# CurrentMonitorOnAStick.net
KiCad netlist of a schematic drawn in EAGLE
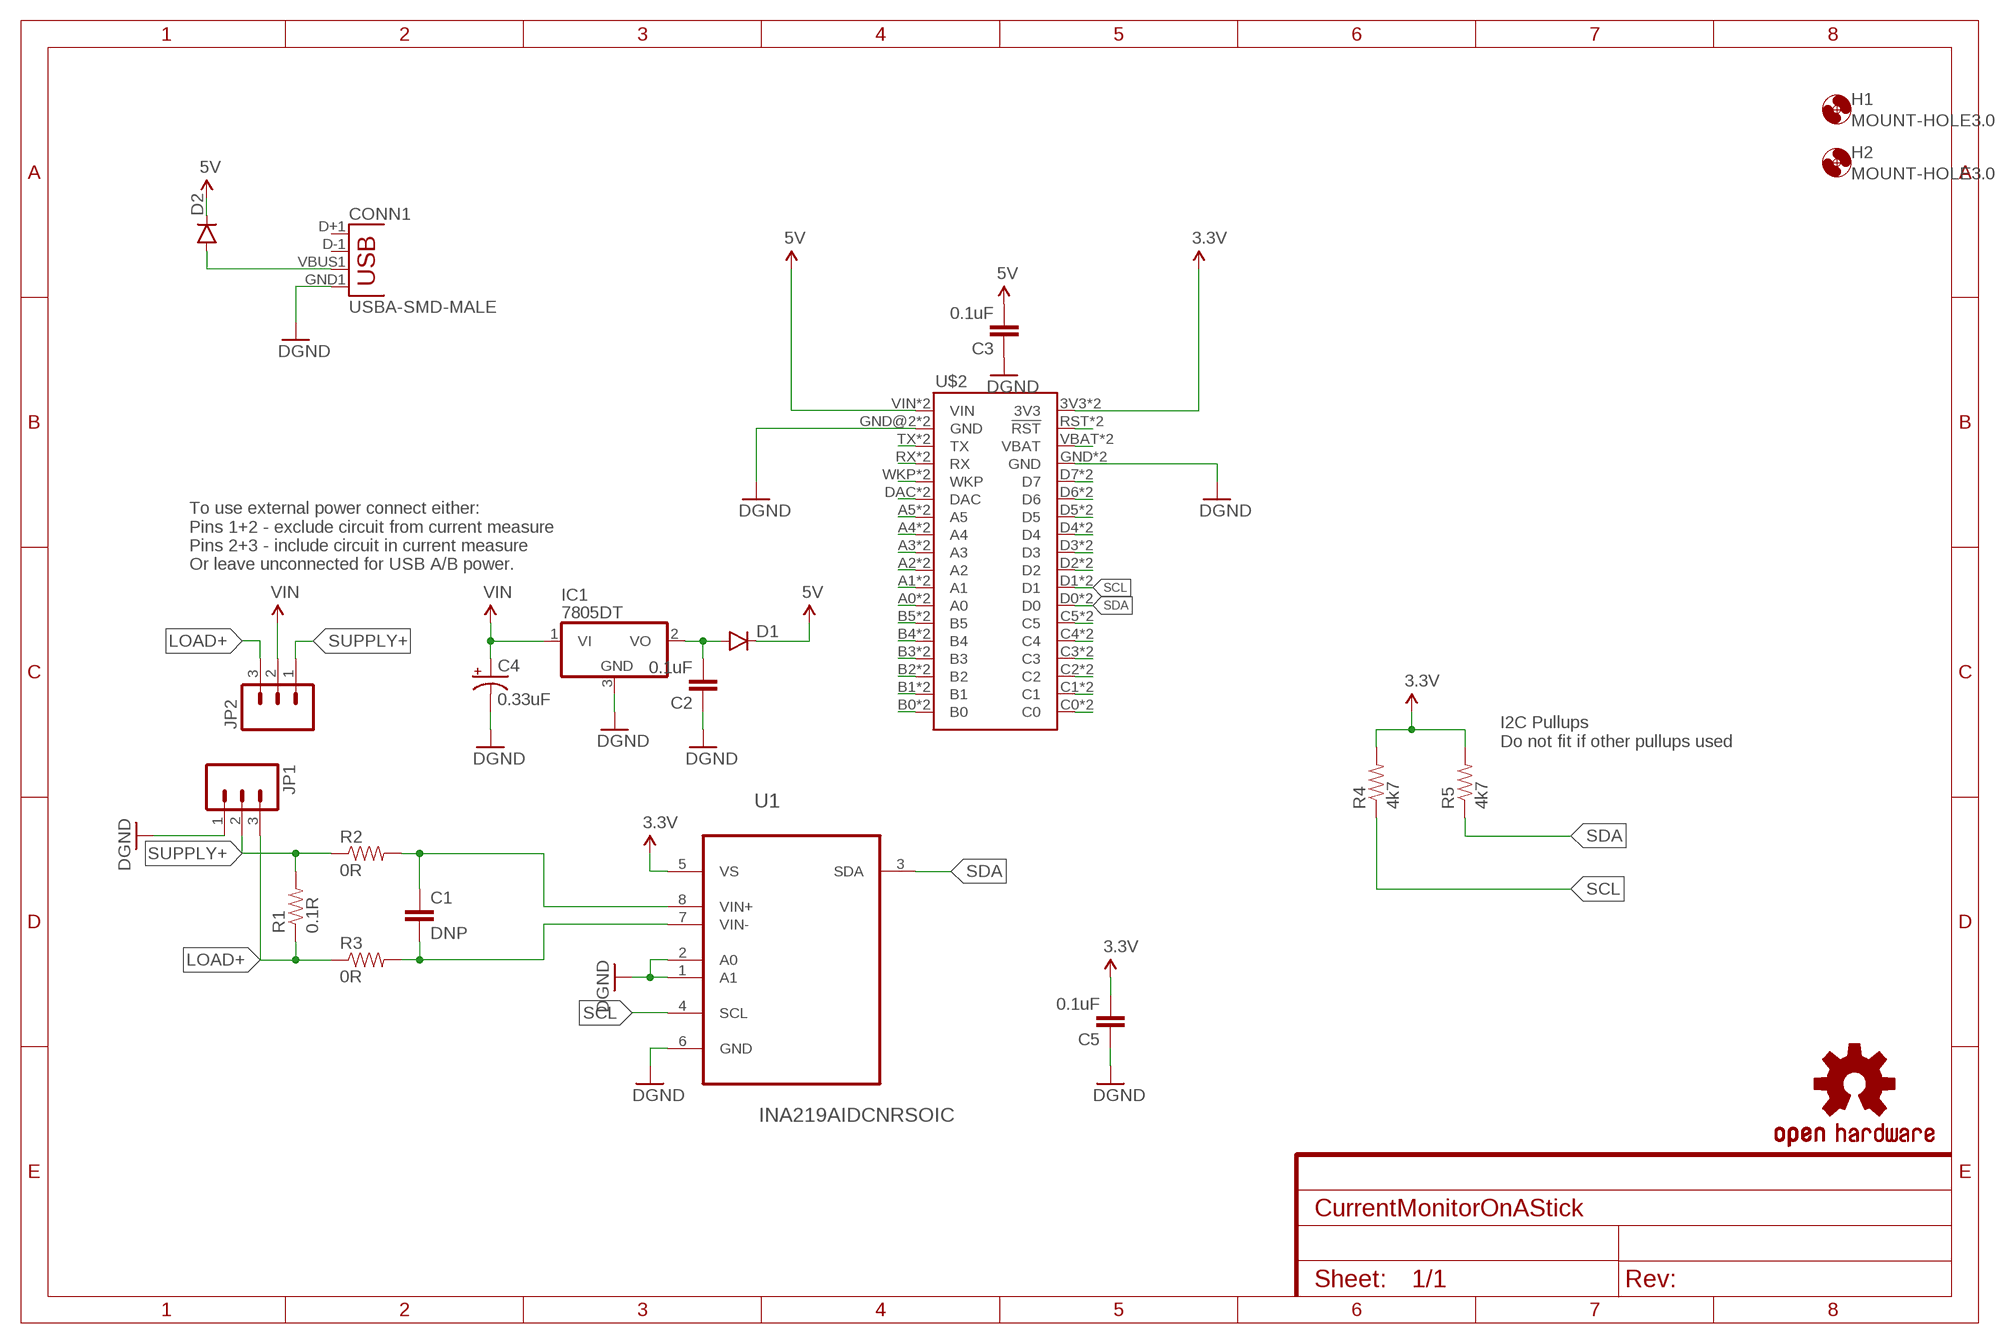
[diagram p0: schematic, sheet 1]

(export (version "E")
  (design (tool "Eeschema 10.0.6"))
  (components
    (comp (ref "C1")
      (value "DNP")
      (footprint "eagle-import:0805")
      (libsource (lib "eagle-import") (part "CAP0805"))
    )
    (comp (ref "C2")
      (value "0.1uF")
      (footprint "eagle-import:0805")
      (libsource (lib "eagle-import") (part "SparkFun-Passives_CAP0805"))
    )
    (comp (ref "C3")
      (value "0.1uF")
      (footprint "eagle-import:0805")
      (libsource (lib "eagle-import") (part "SparkFun-Passives_CAP0805"))
    )
    (comp (ref "C4")
      (value "0.33uF")
      (footprint "eagle-import:EIA3216")
      (libsource (lib "eagle-import") (part "10UF-16V-10%(TANT)"))
    )
    (comp (ref "C5")
      (value "0.1uF")
      (footprint "eagle-import:0805")
      (libsource (lib "eagle-import") (part "SparkFun-Passives_CAP0805"))
    )
    (comp (ref "CONN1")
      (value "USBA-SMD-MALE")
      (footprint "eagle-import:USB-A-SMT-MALE")
      (libsource (lib "eagle-import") (part "USBA-SMD-MALE"))
    )
    (comp (ref "D1")
      (value "DIODESMA")
      (footprint "eagle-import:SMA-DIODE")
      (libsource (lib "eagle-import") (part "DIODESMA"))
    )
    (comp (ref "D2")
      (value "DIODESMA")
      (footprint "eagle-import:SMA-DIODE")
      (libsource (lib "eagle-import") (part "DIODESMA"))
    )
    (comp (ref "H1")
      (value "MOUNT-HOLE3.0")
      (footprint "eagle-import:3,0")
      (libsource (lib "eagle-import") (part "MOUNT-HOLE3.0"))
    )
    (comp (ref "H2")
      (value "MOUNT-HOLE3.0")
      (footprint "eagle-import:3,0")
      (libsource (lib "eagle-import") (part "MOUNT-HOLE3.0"))
    )
    (comp (ref "IC1")
      (value "7805DT")
      (footprint "eagle-import:TO252")
      (libsource (lib "eagle-import") (part "78DT05"))
    )
    (comp (ref "JP1")
      (value "M03-SCREW-5MM")
      (footprint "eagle-import:SCREWTERMINAL-5MM-3")
      (libsource (lib "eagle-import") (part "M03-SCREW-5MM"))
    )
    (comp (ref "JP2")
      (value "M03PTH")
      (footprint "eagle-import:1X03")
      (libsource (lib "eagle-import") (part "M03PTH"))
    )
    (comp (ref "LOGO2")
      (value "OSHW-LOGOS")
      (footprint "eagle-import:OSHW-LOGO-S")
      (libsource (lib "eagle-import") (part "OSHW-LOGOS"))
    )
    (comp (ref "R1")
      (value "0.1R")
      (footprint "eagle-import:2512")
      (libsource (lib "eagle-import") (part "0.001OHM-3W-1%(2512)3W/1%"))
    )
    (comp (ref "R2")
      (value "0R")
      (footprint "eagle-import:0805")
      (libsource (lib "eagle-import") (part "RESISTOR0805-RES"))
    )
    (comp (ref "R3")
      (value "0R")
      (footprint "eagle-import:0805")
      (libsource (lib "eagle-import") (part "RESISTOR0805-RES"))
    )
    (comp (ref "R4")
      (value "4k7")
      (footprint "eagle-import:0805")
      (libsource (lib "eagle-import") (part "RESISTOR0805-RES"))
    )
    (comp (ref "R5")
      (value "4k7")
      (footprint "eagle-import:0805")
      (libsource (lib "eagle-import") (part "RESISTOR0805-RES"))
    )
    (comp (ref "U$2")
      (value "ELECTRONDUALNAMED")
      (footprint "eagle-import:ELECTRON_SIMPLE_SILK_NAMES_DUAL")
      (libsource (lib "eagle-import") (part "ELECTRONDUALNAMED"))
    )
    (comp (ref "U1")
      (value "INA219AIDCNRSOIC")
      (footprint "eagle-import:SO08")
      (libsource (lib "eagle-import") (part "INA219AIDCNRSOIC"))
    )
  )
  (nets
    (net (code "1") (name "3.3V") (class "Default")
      (node (ref "C5") (pin "2") (pinfunction "2_2") (pintype "passive"))
      (node (ref "R4") (pin "2") (pinfunction "2_2") (pintype "passive"))
      (node (ref "R5") (pin "2") (pinfunction "2_2") (pintype "passive"))
      (node (ref "U$2") (pin "3V3") (pinfunction "3V3_3V3") (pintype "power_in"))
      (node (ref "U$2") (pin "3V3_1") (pinfunction "3V3_3V3_1") (pintype "power_in"))
      (node (ref "U1") (pin "5") (pinfunction "VS_5") (pintype "power_in"))
    )
    (net (code "2") (name "5V") (class "Default")
      (node (ref "C3") (pin "2") (pinfunction "2_2") (pintype "passive"))
      (node (ref "D1") (pin "C") (pinfunction "C_C") (pintype "passive"))
      (node (ref "D2") (pin "C") (pinfunction "C_C") (pintype "passive"))
      (node (ref "U$2") (pin "VIN") (pinfunction "VIN_VIN") (pintype "power_in"))
      (node (ref "U$2") (pin "VIN_1B") (pinfunction "VIN_VIN_1B") (pintype "power_in"))
    )
    (net (code "3") (name "DGND") (class "Default")
      (node (ref "C2") (pin "1") (pinfunction "1_1") (pintype "passive"))
      (node (ref "C3") (pin "1") (pinfunction "1_1") (pintype "passive"))
      (node (ref "C4") (pin "C") (pinfunction "-_C") (pintype "passive"))
      (node (ref "C5") (pin "1") (pinfunction "1_1") (pintype "passive"))
      (node (ref "CONN1") (pin "GND1") (pinfunction "GND_GND1") (pintype "bidirectional"))
      (node (ref "IC1") (pin "3") (pinfunction "GND_3") (pintype "passive"))
      (node (ref "JP1") (pin "1") (pinfunction "1_1") (pintype "passive"))
      (node (ref "U$2") (pin "GND") (pinfunction "GND_GND") (pintype "power_in"))
      (node (ref "U$2") (pin "GND@2") (pinfunction "GND_GND@2") (pintype "power_in"))
      (node (ref "U$2") (pin "GND_1") (pinfunction "GND_GND_1") (pintype "power_in"))
      (node (ref "U$2") (pin "GND_1B") (pinfunction "GND_GND_1B") (pintype "power_in"))
      (node (ref "U1") (pin "1") (pinfunction "A1_1") (pintype "input"))
      (node (ref "U1") (pin "2") (pinfunction "A0_2") (pintype "input"))
      (node (ref "U1") (pin "6") (pinfunction "GND_6") (pintype "passive"))
    )
    (net (code "4") (name "LOAD+") (class "Default")
      (node (ref "JP1") (pin "3") (pinfunction "3_3") (pintype "passive"))
      (node (ref "JP2") (pin "3") (pinfunction "3_3") (pintype "passive"))
      (node (ref "R1") (pin "1") (pinfunction "1_1") (pintype "passive"))
      (node (ref "R3") (pin "1") (pinfunction "1_1") (pintype "passive"))
    )
    (net (code "5") (name "Net-(CONN1-VBUS)") (class "Default")
      (node (ref "CONN1") (pin "VBUS1") (pinfunction "VBUS_VBUS1") (pintype "bidirectional"))
      (node (ref "D2") (pin "A") (pinfunction "A_A") (pintype "passive"))
    )
    (net (code "6") (name "Net-(IC1-VO)") (class "Default")
      (node (ref "C2") (pin "2") (pinfunction "2_2") (pintype "passive"))
      (node (ref "D1") (pin "A") (pinfunction "A_A") (pintype "passive"))
      (node (ref "IC1") (pin "2") (pinfunction "VO_2") (pintype "passive"))
    )
    (net (code "7") (name "Net-(U$2-A0-PadA0_1)") (class "Default")
      (node (ref "U$2") (pin "A0") (pinfunction "A0_A0") (pintype "bidirectional"))
      (node (ref "U$2") (pin "A0_1") (pinfunction "A0_A0_1") (pintype "bidirectional"))
    )
    (net (code "8") (name "Net-(U$2-A1-PadA1_1)") (class "Default")
      (node (ref "U$2") (pin "A1") (pinfunction "A1_A1") (pintype "bidirectional"))
      (node (ref "U$2") (pin "A1_1") (pinfunction "A1_A1_1") (pintype "bidirectional"))
    )
    (net (code "9") (name "Net-(U$2-A2-PadA2_1)") (class "Default")
      (node (ref "U$2") (pin "A2") (pinfunction "A2_A2") (pintype "bidirectional"))
      (node (ref "U$2") (pin "A2_1") (pinfunction "A2_A2_1") (pintype "bidirectional"))
    )
    (net (code "10") (name "Net-(U$2-A3-PadA3_1)") (class "Default")
      (node (ref "U$2") (pin "A3") (pinfunction "A3_A3") (pintype "bidirectional"))
      (node (ref "U$2") (pin "A3_1") (pinfunction "A3_A3_1") (pintype "bidirectional"))
    )
    (net (code "11") (name "Net-(U$2-A4-PadA4_1)") (class "Default")
      (node (ref "U$2") (pin "A4") (pinfunction "A4_A4") (pintype "bidirectional"))
      (node (ref "U$2") (pin "A4_1") (pinfunction "A4_A4_1") (pintype "bidirectional"))
    )
    (net (code "12") (name "Net-(U$2-A5-PadA5_1)") (class "Default")
      (node (ref "U$2") (pin "A5") (pinfunction "A5_A5") (pintype "bidirectional"))
      (node (ref "U$2") (pin "A5_1") (pinfunction "A5_A5_1") (pintype "bidirectional"))
    )
    (net (code "13") (name "Net-(U$2-B0-PadB0_1)") (class "Default")
      (node (ref "U$2") (pin "B0") (pinfunction "B0_B0") (pintype "bidirectional"))
      (node (ref "U$2") (pin "B0_1") (pinfunction "B0_B0_1") (pintype "bidirectional"))
    )
    (net (code "14") (name "Net-(U$2-B1-PadB1_1)") (class "Default")
      (node (ref "U$2") (pin "B1") (pinfunction "B1_B1") (pintype "bidirectional"))
      (node (ref "U$2") (pin "B1_1") (pinfunction "B1_B1_1") (pintype "bidirectional"))
    )
    (net (code "15") (name "Net-(U$2-B2-PadB2_1)") (class "Default")
      (node (ref "U$2") (pin "B2") (pinfunction "B2_B2") (pintype "bidirectional"))
      (node (ref "U$2") (pin "B2_1") (pinfunction "B2_B2_1") (pintype "bidirectional"))
    )
    (net (code "16") (name "Net-(U$2-B3-PadB3_1)") (class "Default")
      (node (ref "U$2") (pin "B3") (pinfunction "B3_B3") (pintype "bidirectional"))
      (node (ref "U$2") (pin "B3_1") (pinfunction "B3_B3_1") (pintype "bidirectional"))
    )
    (net (code "17") (name "Net-(U$2-B4-PadB4_1)") (class "Default")
      (node (ref "U$2") (pin "B4") (pinfunction "B4_B4") (pintype "bidirectional"))
      (node (ref "U$2") (pin "B4_1") (pinfunction "B4_B4_1") (pintype "bidirectional"))
    )
    (net (code "18") (name "Net-(U$2-B5-PadB5_1)") (class "Default")
      (node (ref "U$2") (pin "B5") (pinfunction "B5_B5") (pintype "bidirectional"))
      (node (ref "U$2") (pin "B5_1") (pinfunction "B5_B5_1") (pintype "bidirectional"))
    )
    (net (code "19") (name "Net-(U$2-C0-PadC0_1)") (class "Default")
      (node (ref "U$2") (pin "C0") (pinfunction "C0_C0") (pintype "bidirectional"))
      (node (ref "U$2") (pin "C0_1") (pinfunction "C0_C0_1") (pintype "bidirectional"))
    )
    (net (code "20") (name "Net-(U$2-C1-PadC1_1)") (class "Default")
      (node (ref "U$2") (pin "C1") (pinfunction "C1_C1") (pintype "bidirectional"))
      (node (ref "U$2") (pin "C1_1") (pinfunction "C1_C1_1") (pintype "bidirectional"))
    )
    (net (code "21") (name "Net-(U$2-C2-PadC2_1)") (class "Default")
      (node (ref "U$2") (pin "C2") (pinfunction "C2_C2") (pintype "bidirectional"))
      (node (ref "U$2") (pin "C2_1") (pinfunction "C2_C2_1") (pintype "bidirectional"))
    )
    (net (code "22") (name "Net-(U$2-C3-PadC3_1)") (class "Default")
      (node (ref "U$2") (pin "C3") (pinfunction "C3_C3") (pintype "bidirectional"))
      (node (ref "U$2") (pin "C3_1") (pinfunction "C3_C3_1") (pintype "bidirectional"))
    )
    (net (code "23") (name "Net-(U$2-C4-PadC4_1)") (class "Default")
      (node (ref "U$2") (pin "C4") (pinfunction "C4_C4") (pintype "bidirectional"))
      (node (ref "U$2") (pin "C4_1") (pinfunction "C4_C4_1") (pintype "bidirectional"))
    )
    (net (code "24") (name "Net-(U$2-C5-PadC5_1)") (class "Default")
      (node (ref "U$2") (pin "C5") (pinfunction "C5_C5") (pintype "bidirectional"))
      (node (ref "U$2") (pin "C5_1") (pinfunction "C5_C5_1") (pintype "bidirectional"))
    )
    (net (code "25") (name "Net-(U$2-D2-PadD2_1)") (class "Default")
      (node (ref "U$2") (pin "D2") (pinfunction "D2_D2") (pintype "bidirectional"))
      (node (ref "U$2") (pin "D2_1") (pinfunction "D2_D2_1") (pintype "bidirectional"))
    )
    (net (code "26") (name "Net-(U$2-D3-PadD3_1)") (class "Default")
      (node (ref "U$2") (pin "D3") (pinfunction "D3_D3") (pintype "bidirectional"))
      (node (ref "U$2") (pin "D3_1") (pinfunction "D3_D3_1") (pintype "bidirectional"))
    )
    (net (code "27") (name "Net-(U$2-D4-PadD4_1)") (class "Default")
      (node (ref "U$2") (pin "D4") (pinfunction "D4_D4") (pintype "bidirectional"))
      (node (ref "U$2") (pin "D4_1") (pinfunction "D4_D4_1") (pintype "bidirectional"))
    )
    (net (code "28") (name "Net-(U$2-D5-PadD5_1)") (class "Default")
      (node (ref "U$2") (pin "D5") (pinfunction "D5_D5") (pintype "bidirectional"))
      (node (ref "U$2") (pin "D5_1") (pinfunction "D5_D5_1") (pintype "bidirectional"))
    )
    (net (code "29") (name "Net-(U$2-D6-PadD6_1)") (class "Default")
      (node (ref "U$2") (pin "D6") (pinfunction "D6_D6") (pintype "bidirectional"))
      (node (ref "U$2") (pin "D6_1") (pinfunction "D6_D6_1") (pintype "bidirectional"))
    )
    (net (code "30") (name "Net-(U$2-D7-PadD7_1)") (class "Default")
      (node (ref "U$2") (pin "D7") (pinfunction "D7_D7") (pintype "bidirectional"))
      (node (ref "U$2") (pin "D7_1") (pinfunction "D7_D7_1") (pintype "bidirectional"))
    )
    (net (code "31") (name "Net-(U$2-DAC-PadDAC_1)") (class "Default")
      (node (ref "U$2") (pin "DAC") (pinfunction "DAC_DAC") (pintype "bidirectional"))
      (node (ref "U$2") (pin "DAC_1") (pinfunction "DAC_DAC_1") (pintype "bidirectional"))
    )
    (net (code "32") (name "Net-(U$2-PadRX)") (class "Default")
      (node (ref "U$2") (pin "RX") (pinfunction "RX_RX") (pintype "bidirectional"))
      (node (ref "U$2") (pin "RX_1") (pinfunction "RX_RX_1") (pintype "bidirectional"))
    )
    (net (code "33") (name "Net-(U$2-PadTX)") (class "Default")
      (node (ref "U$2") (pin "TX") (pinfunction "TX_TX") (pintype "bidirectional"))
      (node (ref "U$2") (pin "TX_1") (pinfunction "TX_TX_1") (pintype "bidirectional"))
    )
    (net (code "34") (name "Net-(U$2-PadVBAT)") (class "Default")
      (node (ref "U$2") (pin "VBAT") (pinfunction "VBAT_VBAT") (pintype "passive"))
      (node (ref "U$2") (pin "VBATT_1") (pinfunction "VBAT_VBATT_1") (pintype "passive"))
    )
    (net (code "35") (name "Net-(U$2-PadWKP)") (class "Default")
      (node (ref "U$2") (pin "WKP") (pinfunction "WKP_WKP") (pintype "bidirectional"))
      (node (ref "U$2") (pin "WKP_1") (pinfunction "WKP_WKP_1") (pintype "bidirectional"))
    )
    (net (code "36") (name "Net-(U$2-~{RST}-PadRST)") (class "Default")
      (node (ref "U$2") (pin "RST") (pinfunction "~{RST}_RST") (pintype "bidirectional"))
      (node (ref "U$2") (pin "RST_1") (pinfunction "~{RST}_RST_1") (pintype "bidirectional"))
    )
    (net (code "37") (name "Net-(U1-VIN+)") (class "Default")
      (node (ref "C1") (pin "1") (pinfunction "1_1") (pintype "passive"))
      (node (ref "R2") (pin "2") (pinfunction "2_2") (pintype "passive"))
      (node (ref "U1") (pin "8") (pinfunction "VIN+_8") (pintype "input"))
    )
    (net (code "38") (name "Net-(U1-VIN-)") (class "Default")
      (node (ref "C1") (pin "2") (pinfunction "2_2") (pintype "passive"))
      (node (ref "R3") (pin "2") (pinfunction "2_2") (pintype "passive"))
      (node (ref "U1") (pin "7") (pinfunction "VIN-_7") (pintype "input"))
    )
    (net (code "39") (name "SCL") (class "Default")
      (node (ref "R4") (pin "1") (pinfunction "1_1") (pintype "passive"))
      (node (ref "U$2") (pin "D1") (pinfunction "D1_D1") (pintype "bidirectional"))
      (node (ref "U$2") (pin "D1_1") (pinfunction "D1_D1_1") (pintype "bidirectional"))
      (node (ref "U1") (pin "4") (pinfunction "SCL_4") (pintype "input"))
    )
    (net (code "40") (name "SDA") (class "Default")
      (node (ref "R5") (pin "1") (pinfunction "1_1") (pintype "passive"))
      (node (ref "U$2") (pin "D0") (pinfunction "D0_D0") (pintype "bidirectional"))
      (node (ref "U$2") (pin "D0_1") (pinfunction "D0_D0_1") (pintype "bidirectional"))
      (node (ref "U1") (pin "3") (pinfunction "SDA_3") (pintype "bidirectional"))
    )
    (net (code "41") (name "SUPPLY+") (class "Default")
      (node (ref "JP1") (pin "2") (pinfunction "2_2") (pintype "passive"))
      (node (ref "JP2") (pin "1") (pinfunction "1_1") (pintype "passive"))
      (node (ref "R1") (pin "2") (pinfunction "2_2") (pintype "passive"))
      (node (ref "R2") (pin "1") (pinfunction "1_1") (pintype "passive"))
    )
    (net (code "42") (name "VIN") (class "Default")
      (node (ref "C4") (pin "A") (pinfunction "+_A") (pintype "passive"))
      (node (ref "IC1") (pin "1") (pinfunction "VI_1") (pintype "input"))
      (node (ref "JP2") (pin "2") (pinfunction "2_2") (pintype "passive"))
    )
    (net (code "43") (name "unconnected-(CONN1-D+-PadD+1)") (class "Default")
      (node (ref "CONN1") (pin "D+1") (pinfunction "D+_D+1") (pintype "bidirectional"))
    )
    (net (code "44") (name "unconnected-(CONN1-D--PadD-1)") (class "Default")
      (node (ref "CONN1") (pin "D-1") (pinfunction "D-_D-1") (pintype "bidirectional"))
    )
  )
)
